# ALU_Reg.net
KiCad netlist of a schematic drawn in Altium Designer
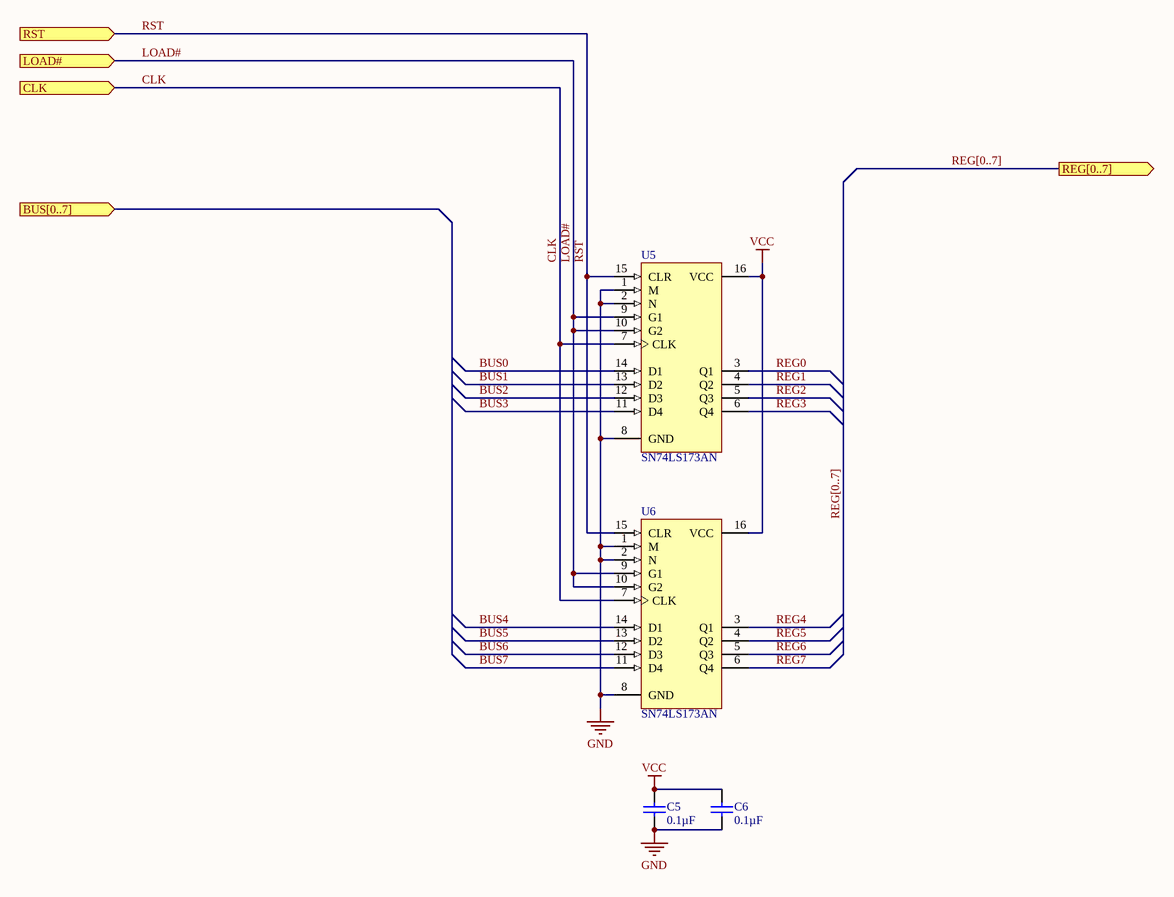
[diagram p0: ALU_Reg.SchDoc]

(export (version "E")
  (design (tool "Eeschema 10.0.6"))
  (components
    (comp (ref "C5")
      (value "K104K15X7RF5TL2")
      (footprint "VISH-K104K15X7RF5TL2")
      (description "Ceramic Capacitor, 100 nF, +/- 10%, 50 V, -55 to 125 degC, 2-Pin THD, RoHS, Tape and Reel")
      (fields
        (field (name "MANUFACTURER") "Vishay")
        (field (name "TOLERANCE") "±10%")
        (field (name "CAPACITANCE") "0.1µF")
      )
      (libsource (lib "Altium Content Vault") (part "CAP-NP-2"))
    )
    (comp (ref "C6")
      (value "K104K15X7RF5TL2")
      (footprint "VISH-K104K15X7RF5TL2")
      (description "Ceramic Capacitor, 100 nF, +/- 10%, 50 V, -55 to 125 degC, 2-Pin THD, RoHS, Tape and Reel")
      (fields
        (field (name "MANUFACTURER") "Vishay")
        (field (name "TOLERANCE") "±10%")
        (field (name "CAPACITANCE") "0.1µF")
      )
      (libsource (lib "Altium Content Vault") (part "CAP-NP-2"))
    )
    (comp (ref "U5")
      (value "SN74LS173AN")
      (footprint "N016D")
      (description "4-Bit D-Type Register with 3-State Outputs")
      (fields (field (name "PUBLISHER") "Altium Limited"))
      (libsource (lib "TI Logic Flip-Flop") (part "SN74LS173AN"))
    )
    (comp (ref "U6")
      (value "SN74LS173AN")
      (footprint "N016D")
      (description "4-Bit D-Type Register with 3-State Outputs")
      (fields (field (name "PUBLISHER") "Altium Limited"))
      (libsource (lib "TI Logic Flip-Flop") (part "SN74LS173AN"))
    )
  )
  (nets
    (net (code "1") (name "/BUS0") (class "Default")
      (node (ref "U5") (pin "14") (pinfunction "D1_14") (pintype "input"))
    )
    (net (code "2") (name "/BUS1") (class "Default")
      (node (ref "U5") (pin "13") (pinfunction "D2_13") (pintype "input"))
    )
    (net (code "3") (name "/BUS2") (class "Default")
      (node (ref "U5") (pin "12") (pinfunction "D3_12") (pintype "input"))
    )
    (net (code "4") (name "/BUS3") (class "Default")
      (node (ref "U5") (pin "11") (pinfunction "D4_11") (pintype "input"))
    )
    (net (code "5") (name "/BUS4") (class "Default")
      (node (ref "U6") (pin "14") (pinfunction "D1_14") (pintype "input"))
    )
    (net (code "6") (name "/BUS5") (class "Default")
      (node (ref "U6") (pin "13") (pinfunction "D2_13") (pintype "input"))
    )
    (net (code "7") (name "/BUS6") (class "Default")
      (node (ref "U6") (pin "12") (pinfunction "D3_12") (pintype "input"))
    )
    (net (code "8") (name "/BUS7") (class "Default")
      (node (ref "U6") (pin "11") (pinfunction "D4_11") (pintype "input"))
    )
    (net (code "10") (name "/CLK") (class "Default")
      (node (ref "U5") (pin "7") (pinfunction "CLK_7") (pintype "input"))
      (node (ref "U6") (pin "7") (pinfunction "CLK_7") (pintype "input"))
    )
    (net (code "11") (name "/LOAD#") (class "Default")
      (node (ref "U5") (pin "10") (pinfunction "G2_10") (pintype "input"))
      (node (ref "U5") (pin "9") (pinfunction "G1_9") (pintype "input"))
      (node (ref "U6") (pin "10") (pinfunction "G2_10") (pintype "input"))
      (node (ref "U6") (pin "9") (pinfunction "G1_9") (pintype "input"))
    )
    (net (code "12") (name "/REG0") (class "Default")
      (node (ref "U5") (pin "3") (pinfunction "Q1_3") (pintype "tri_state"))
    )
    (net (code "13") (name "/REG1") (class "Default")
      (node (ref "U5") (pin "4") (pinfunction "Q2_4") (pintype "tri_state"))
    )
    (net (code "14") (name "/REG2") (class "Default")
      (node (ref "U5") (pin "5") (pinfunction "Q3_5") (pintype "tri_state"))
    )
    (net (code "15") (name "/REG3") (class "Default")
      (node (ref "U5") (pin "6") (pinfunction "Q4_6") (pintype "tri_state"))
    )
    (net (code "16") (name "/REG4") (class "Default")
      (node (ref "U6") (pin "3") (pinfunction "Q1_3") (pintype "tri_state"))
    )
    (net (code "17") (name "/REG5") (class "Default")
      (node (ref "U6") (pin "4") (pinfunction "Q2_4") (pintype "tri_state"))
    )
    (net (code "18") (name "/REG6") (class "Default")
      (node (ref "U6") (pin "5") (pinfunction "Q3_5") (pintype "tri_state"))
    )
    (net (code "19") (name "/REG7") (class "Default")
      (node (ref "U6") (pin "6") (pinfunction "Q4_6") (pintype "tri_state"))
    )
    (net (code "21") (name "/RST") (class "Default")
      (node (ref "U5") (pin "15") (pinfunction "CLR_15") (pintype "input"))
      (node (ref "U6") (pin "15") (pinfunction "CLR_15") (pintype "input"))
    )
    (net (code "22") (name "GND") (class "Default")
      (node (ref "C5") (pin "2") (pinfunction "2_2") (pintype "passive"))
      (node (ref "C6") (pin "2") (pinfunction "2_2") (pintype "passive"))
      (node (ref "U5") (pin "1") (pinfunction "M_1") (pintype "input"))
      (node (ref "U5") (pin "2") (pinfunction "N_2") (pintype "input"))
      (node (ref "U5") (pin "8") (pinfunction "GND_8") (pintype "power_in"))
      (node (ref "U6") (pin "1") (pinfunction "M_1") (pintype "input"))
      (node (ref "U6") (pin "2") (pinfunction "N_2") (pintype "input"))
      (node (ref "U6") (pin "8") (pinfunction "GND_8") (pintype "power_in"))
    )
    (net (code "23") (name "VCC") (class "Default")
      (node (ref "C5") (pin "1") (pinfunction "1_1") (pintype "passive"))
      (node (ref "C6") (pin "1") (pinfunction "1_1") (pintype "passive"))
      (node (ref "U5") (pin "16") (pinfunction "VCC_16") (pintype "power_in"))
      (node (ref "U6") (pin "16") (pinfunction "VCC_16") (pintype "power_in"))
    )
  )
)
